# Engine_Sensors_Breakaway.net
KiCad netlist of a schematic drawn in Altium Designer
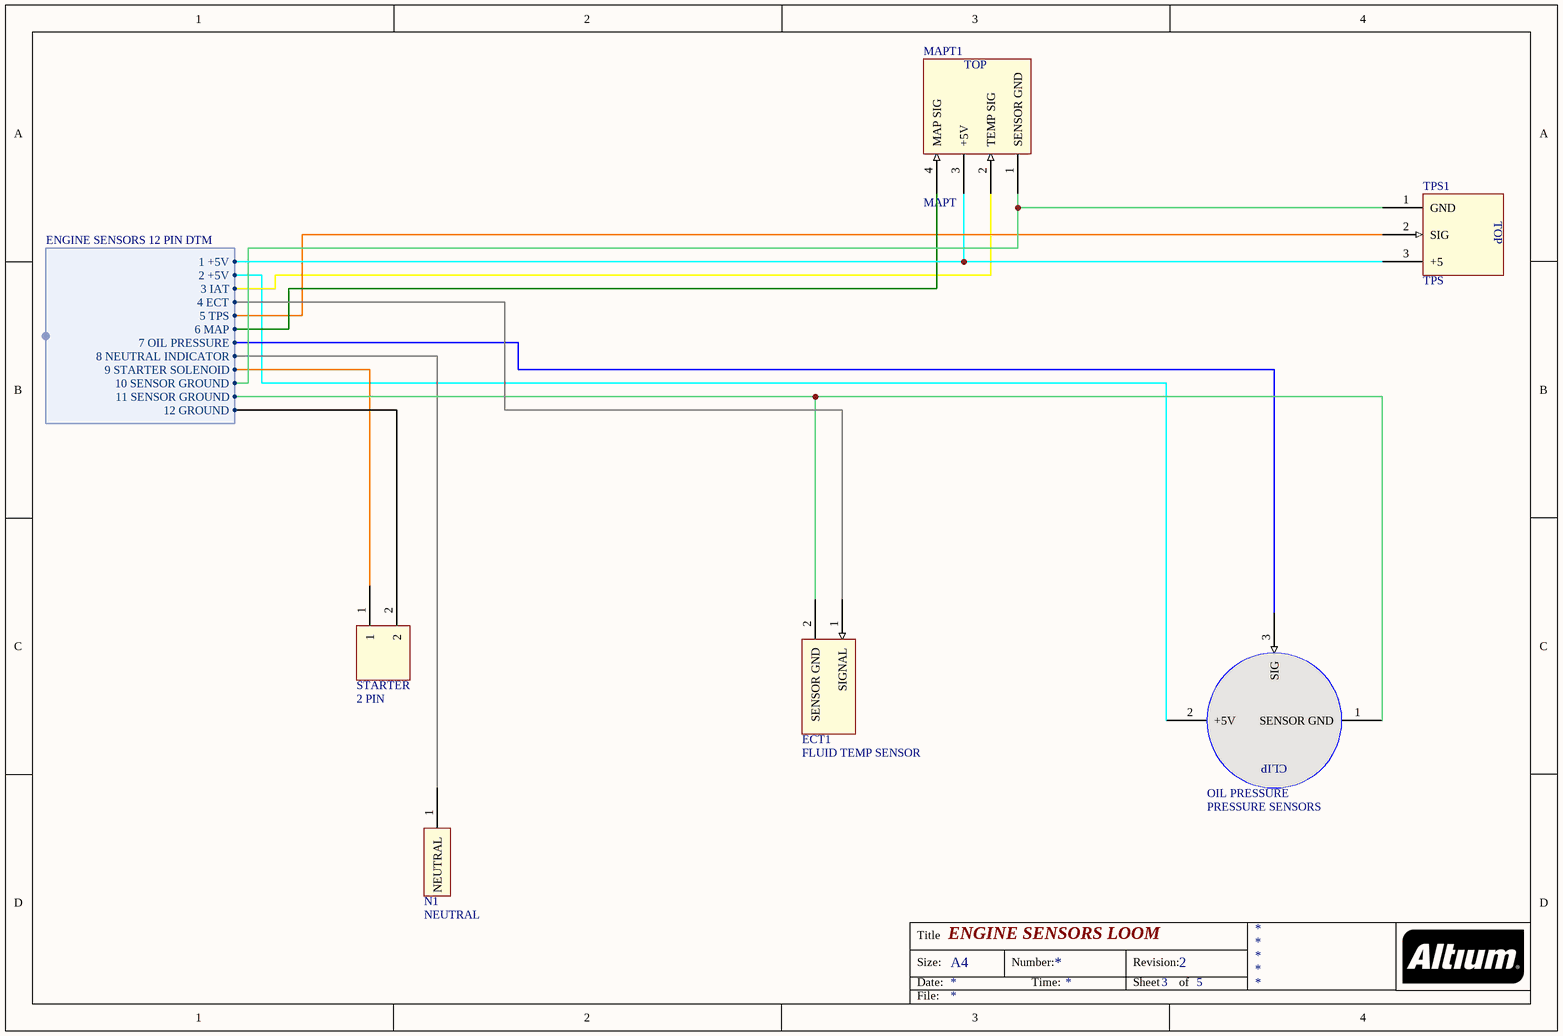
[diagram p0: Engine Sensors Breakaway.SchDoc]

(export (version "E")
  (design (tool "Eeschema 10.0.6"))
  (components
    (comp (ref "ECT1")
      (value "FLUID TEMP SENSOR")
      (description "FOR OIL, FUEL, WATER")
      (libsource (lib "Loom Components") (part "FLUID TEMP SENSOR"))
    )
    (comp (ref "MAPT1")
      (value "MAPT")
      (description "BOSCH 4 BAR MAP AND TEMP")
      (libsource (lib "Loom Components") (part "MAPT"))
    )
    (comp (ref "N1") (value "NEUTRAL") (libsource (lib "Loom Components") (part "NEUTRAL")))
    (comp (ref "OIL PRESSURE")
      (value "PRESSURE SENSORS")
      (description "TEXAS INSTRUMENTS 150 PSI")
      (libsource (lib "Loom Components") (part "PRESSURE SENSORS"))
    )
    (comp (ref "STARTER") (value "2 PIN") (libsource (lib "Loom Connectors") (part "2 PIN")))
    (comp (ref "TPS1")
      (value "TPS")
      (description "ACUITY HALL EFFECT TPS")
      (libsource (lib "Loom Components") (part "TPS"))
    )
  )
  (nets
    (net (code "1") (name "/1 +5V") (class "Default")
      (node (ref "MAPT1") (pin "3") (pinfunction "+5V_3") (pintype "power_in"))
      (node (ref "TPS1") (pin "3") (pinfunction "+5_3") (pintype "passive"))
    )
    (net (code "2") (name "/2 +5V") (class "Default")
      (node (ref "OIL PRESSURE") (pin "2") (pinfunction "+5V_2") (pintype "power_in"))
    )
    (net (code "3") (name "/3 IAT") (class "Default")
      (node (ref "MAPT1") (pin "2") (pinfunction "TEMP_SIG_2") (pintype "input"))
    )
    (net (code "4") (name "/4 ECT") (class "Default")
      (node (ref "ECT1") (pin "1") (pinfunction "SIGNAL_1") (pintype "input"))
    )
    (net (code "5") (name "/5 TPS") (class "Default")
      (node (ref "TPS1") (pin "2") (pinfunction "SIG_2") (pintype "input"))
    )
    (net (code "6") (name "/6 MAP") (class "Default")
      (node (ref "MAPT1") (pin "4") (pinfunction "MAP_SIG_4") (pintype "input"))
    )
    (net (code "7") (name "/7 OIL PRESSURE") (class "Default")
      (node (ref "OIL PRESSURE") (pin "3") (pinfunction "SIG_3") (pintype "input"))
    )
    (net (code "8") (name "/8 NEUTRAL INDICATOR") (class "Default")
      (node (ref "N1") (pin "1") (pinfunction "NEUTRAL_1") (pintype "passive"))
    )
    (net (code "9") (name "/9 STARTER SOLENOID") (class "Default")
      (node (ref "STARTER") (pin "1") (pinfunction "1_1") (pintype "passive"))
    )
    (net (code "10") (name "/10 SENSOR GROUND") (class "Default")
      (node (ref "MAPT1") (pin "1") (pinfunction "SENSOR_GND_1") (pintype "power_in"))
      (node (ref "TPS1") (pin "1") (pinfunction "GND_1") (pintype "passive"))
    )
    (net (code "11") (name "/11 SENSOR GROUND") (class "Default")
      (node (ref "ECT1") (pin "2") (pinfunction "SENSOR_GND_2") (pintype "power_in"))
      (node (ref "OIL PRESSURE") (pin "1") (pinfunction "SENSOR_GND_1") (pintype "power_in"))
    )
    (net (code "12") (name "/12 GROUND") (class "Default")
      (node (ref "STARTER") (pin "2") (pinfunction "2_2") (pintype "passive"))
    )
  )
)
